# Power_supply.net
KiCad netlist of a schematic drawn in EAGLE
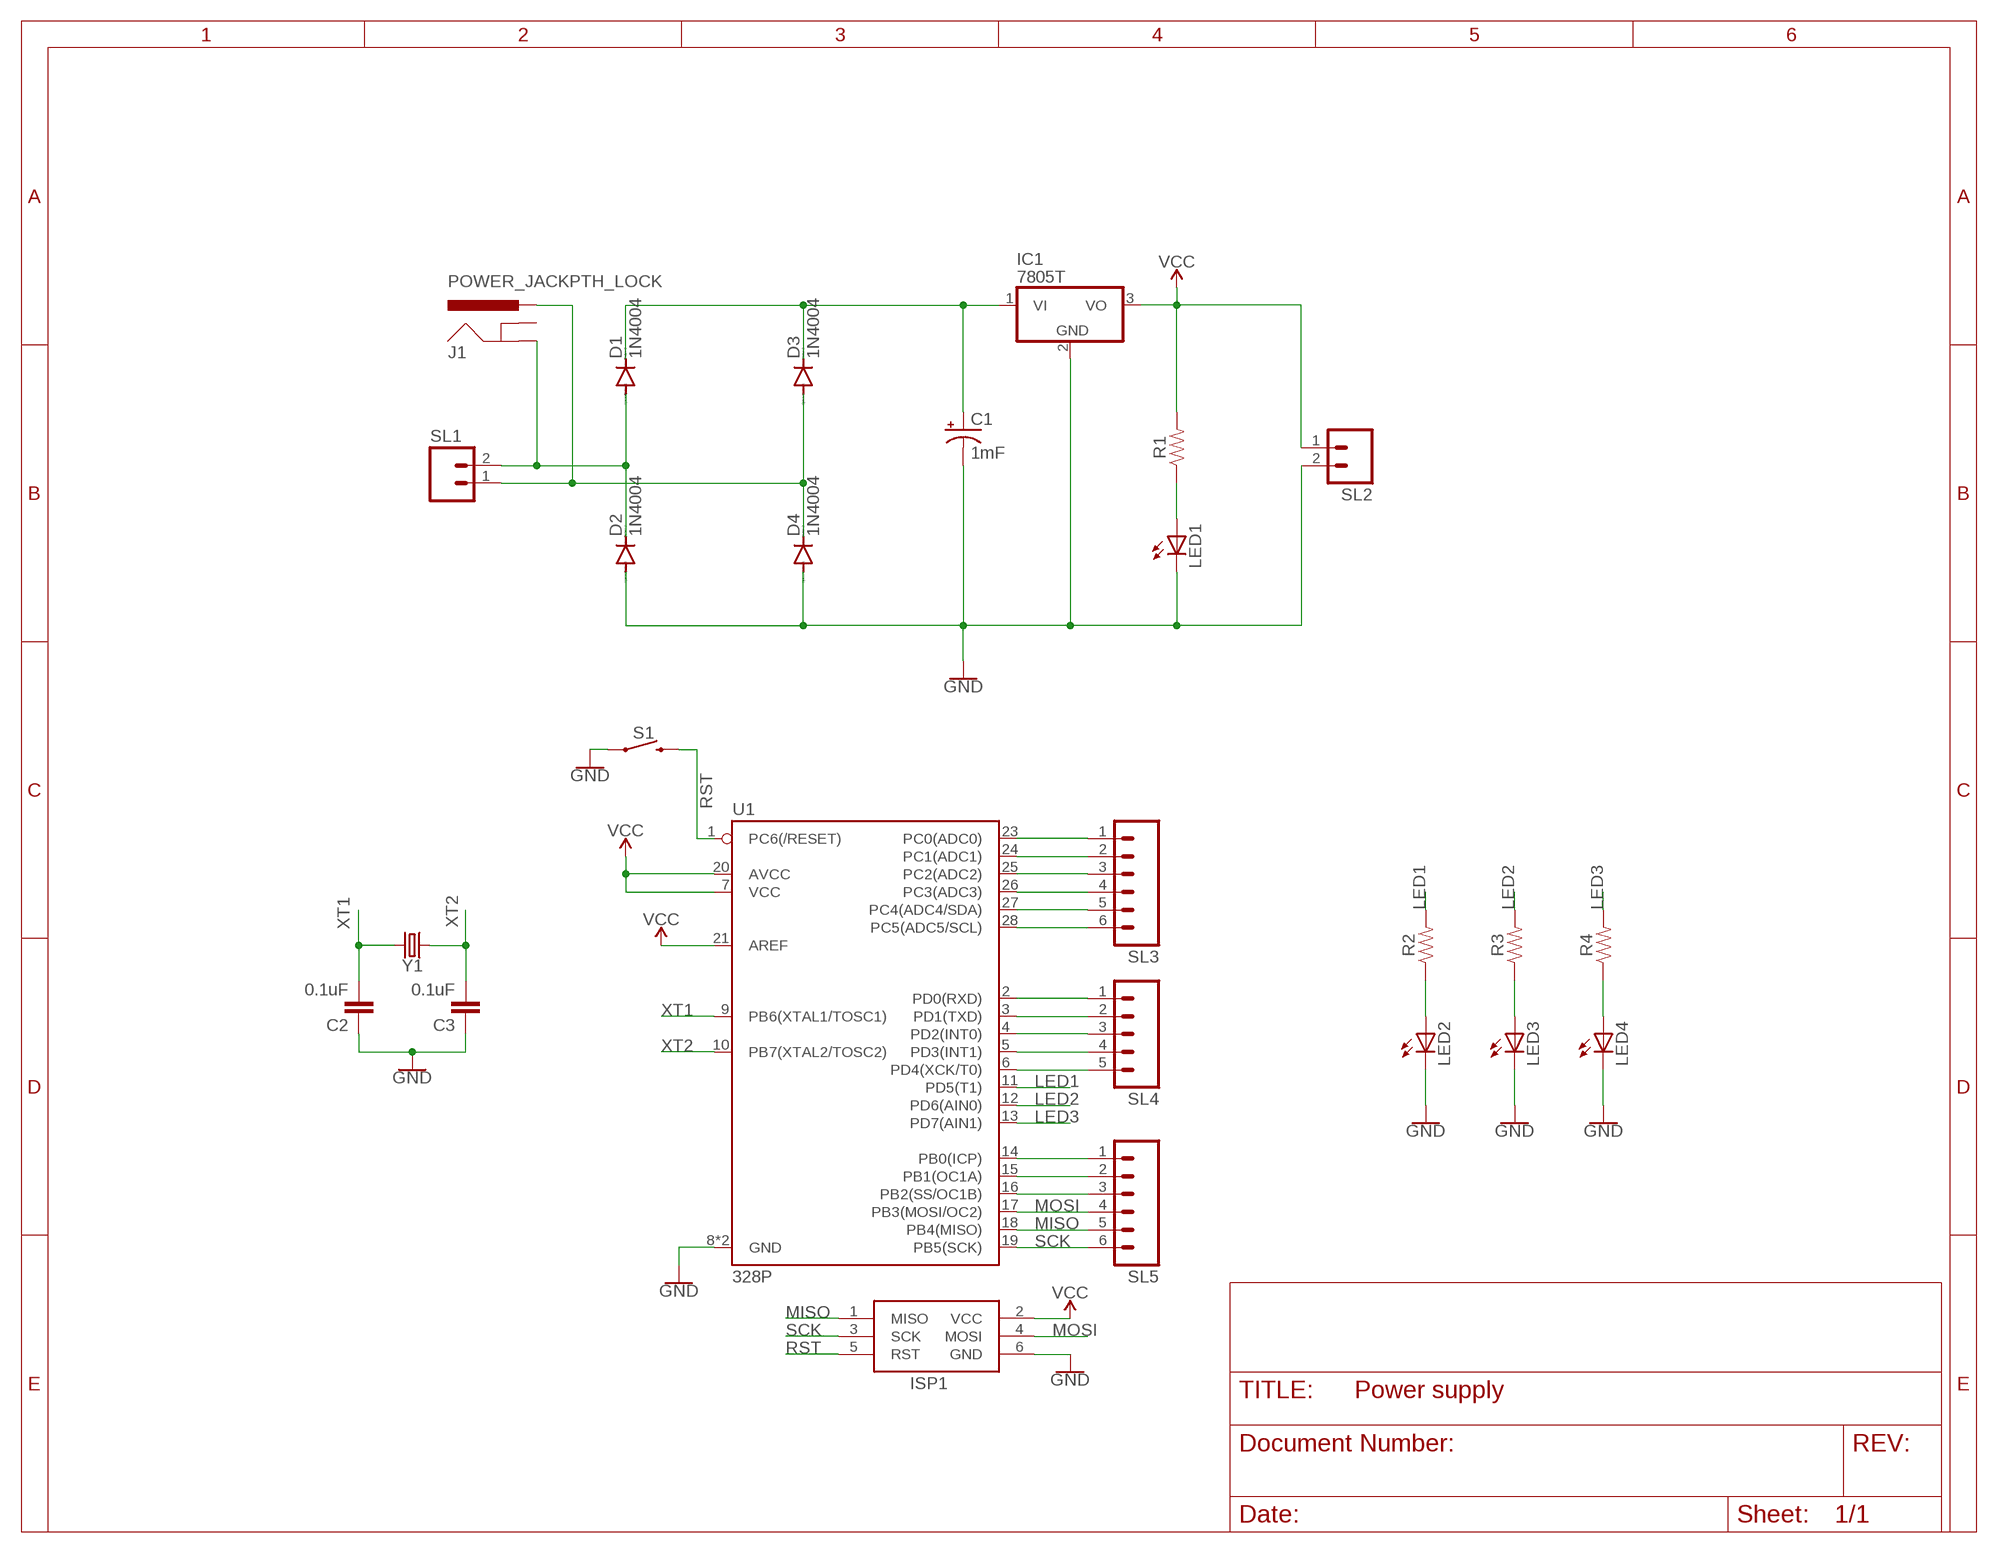
[diagram p0: schematic, sheet 1]

(export (version "E")
  (design (tool "Eeschema 10.0.6"))
  (components
    (comp (ref "C1")
      (value "1mF")
      (footprint "eagle-import:CPOL-RADIAL-5MM-10MM")
      (libsource (lib "eagle-import") (part "1000UF-RADIAL-5MM-25V-20%"))
    )
    (comp (ref "C2")
      (value "0.1uF")
      (footprint "eagle-import:CAP-PTH-SMALL-KIT")
      (libsource (lib "eagle-import") (part "0.1UF-KIT-EZ-50V-20%"))
    )
    (comp (ref "C3")
      (value "0.1uF")
      (footprint "eagle-import:CAP-PTH-SMALL-KIT")
      (libsource (lib "eagle-import") (part "0.1UF-KIT-EZ-50V-20%"))
    )
    (comp (ref "D1")
      (value "1N4004")
      (footprint "eagle-import:DO41-10")
      (libsource (lib "eagle-import") (part "1N4004"))
    )
    (comp (ref "D2")
      (value "1N4004")
      (footprint "eagle-import:DO41-10")
      (libsource (lib "eagle-import") (part "1N4004"))
    )
    (comp (ref "D3")
      (value "1N4004")
      (footprint "eagle-import:DO41-10")
      (libsource (lib "eagle-import") (part "1N4004"))
    )
    (comp (ref "D4")
      (value "1N4004")
      (footprint "eagle-import:DO41-10")
      (libsource (lib "eagle-import") (part "1N4004"))
    )
    (comp (ref "IC1")
      (value "7805T")
      (footprint "eagle-import:TO220H")
      (libsource (lib "eagle-import") (part "78T05"))
    )
    (comp (ref "ISP1")
      (value "AVRISP-6")
      (footprint "eagle-import:AVRISP")
      (libsource (lib "eagle-import") (part "AVRISP-6"))
    )
    (comp (ref "J1")
      (value "POWER_JACKPTH_LOCK")
      (footprint "eagle-import:POWER_JACK_PTH_LOCK")
      (libsource (lib "eagle-import") (part "POWER_JACKPTH_LOCK"))
    )
    (comp (ref "LED1")
      (value "LED5MM")
      (footprint "eagle-import:LED5MM")
      (libsource (lib "eagle-import") (part "LED5MM"))
    )
    (comp (ref "LED2")
      (value "LED3MM")
      (footprint "eagle-import:LED3MM")
      (libsource (lib "eagle-import") (part "LED3MM"))
    )
    (comp (ref "LED3")
      (value "LED3MM")
      (footprint "eagle-import:LED3MM")
      (libsource (lib "eagle-import") (part "LED3MM"))
    )
    (comp (ref "LED4")
      (value "LED3MM")
      (footprint "eagle-import:LED3MM")
      (libsource (lib "eagle-import") (part "LED3MM"))
    )
    (comp (ref "R1")
      (value "RESISTORAXIAL-0.3")
      (footprint "eagle-import:AXIAL-0.3")
      (libsource (lib "eagle-import") (part "RESISTORAXIAL-0.3"))
    )
    (comp (ref "R2")
      (value "RESISTORAXIAL-0.3")
      (footprint "eagle-import:AXIAL-0.3")
      (libsource (lib "eagle-import") (part "RESISTORAXIAL-0.3"))
    )
    (comp (ref "R3")
      (value "RESISTORAXIAL-0.3")
      (footprint "eagle-import:AXIAL-0.3")
      (libsource (lib "eagle-import") (part "RESISTORAXIAL-0.3"))
    )
    (comp (ref "R4")
      (value "RESISTORAXIAL-0.3")
      (footprint "eagle-import:AXIAL-0.3")
      (libsource (lib "eagle-import") (part "RESISTORAXIAL-0.3"))
    )
    (comp (ref "S1")
      (value "MOMENTARY-SWITCH-SPST-PTH-6.0MM")
      (footprint "eagle-import:TACTILE_SWITCH_PTH_6.0MM")
      (libsource (lib "eagle-import") (part "MOMENTARY-SWITCH-SPST-PTH-6.0MM"))
    )
    (comp (ref "SL1")
      (value "M02")
      (footprint "eagle-import:02P")
      (libsource (lib "eagle-import") (part "M02"))
    )
    (comp (ref "SL2")
      (value "M02")
      (footprint "eagle-import:02P")
      (libsource (lib "eagle-import") (part "M02"))
    )
    (comp (ref "SL3")
      (value "M06")
      (footprint "eagle-import:06P")
      (libsource (lib "eagle-import") (part "M06"))
    )
    (comp (ref "SL4")
      (value "M05")
      (footprint "eagle-import:05P")
      (libsource (lib "eagle-import") (part "M05"))
    )
    (comp (ref "SL5")
      (value "M06")
      (footprint "eagle-import:06P")
      (libsource (lib "eagle-import") (part "M06"))
    )
    (comp (ref "U1")
      (value "328P")
      (footprint "eagle-import:DIP28")
      (libsource (lib "eagle-import") (part "ATMEGA328P_PDIP"))
    )
    (comp (ref "Y1")
      (value "CRYSTALPTH-HC49US")
      (footprint "eagle-import:HC49US")
      (libsource (lib "eagle-import") (part "CRYSTALPTH-HC49US"))
    )
  )
  (nets
    (net (code "1") (name "/LED1") (class "Default")
      (node (ref "R2") (pin "P$2") (pinfunction "2_P$2") (pintype "passive"))
      (node (ref "U1") (pin "11") (pinfunction "PD5(T1)_11") (pintype "bidirectional"))
    )
    (net (code "2") (name "/LED2") (class "Default")
      (node (ref "R3") (pin "P$2") (pinfunction "2_P$2") (pintype "passive"))
      (node (ref "U1") (pin "12") (pinfunction "PD6(AIN0)_12") (pintype "bidirectional"))
    )
    (net (code "3") (name "/LED3") (class "Default")
      (node (ref "R4") (pin "P$2") (pinfunction "2_P$2") (pintype "passive"))
      (node (ref "U1") (pin "13") (pinfunction "PD7(AIN1)_13") (pintype "bidirectional"))
    )
    (net (code "4") (name "/MISO") (class "Default")
      (node (ref "ISP1") (pin "1") (pinfunction "MISO_1") (pintype "input"))
      (node (ref "SL5") (pin "5") (pinfunction "5_5") (pintype "passive"))
      (node (ref "U1") (pin "18") (pinfunction "PB4(MISO)_18") (pintype "bidirectional"))
    )
    (net (code "5") (name "/MOSI") (class "Default")
      (node (ref "ISP1") (pin "4") (pinfunction "MOSI_4") (pintype "output"))
      (node (ref "SL5") (pin "4") (pinfunction "4_4") (pintype "passive"))
      (node (ref "U1") (pin "17") (pinfunction "PB3(MOSI/OC2)_17") (pintype "bidirectional"))
    )
    (net (code "6") (name "/RST") (class "Default")
      (node (ref "ISP1") (pin "5") (pinfunction "RST_5") (pintype "output"))
      (node (ref "S1") (pin "3") (pinfunction "2_3") (pintype "passive"))
      (node (ref "U1") (pin "1") (pinfunction "PC6(/RESET)_1") (pintype "bidirectional"))
    )
    (net (code "7") (name "/SCK") (class "Default")
      (node (ref "ISP1") (pin "3") (pinfunction "SCK_3") (pintype "output"))
      (node (ref "SL5") (pin "6") (pinfunction "6_6") (pintype "passive"))
      (node (ref "U1") (pin "19") (pinfunction "PB5(SCK)_19") (pintype "bidirectional"))
    )
    (net (code "8") (name "/XT1") (class "Default")
      (node (ref "C2") (pin "2") (pinfunction "2_2") (pintype "passive"))
      (node (ref "U1") (pin "9") (pinfunction "PB6(XTAL1/TOSC1)_9") (pintype "bidirectional"))
      (node (ref "Y1") (pin "2") (pinfunction "2_2") (pintype "passive"))
    )
    (net (code "9") (name "/XT2") (class "Default")
      (node (ref "C3") (pin "2") (pinfunction "2_2") (pintype "passive"))
      (node (ref "U1") (pin "10") (pinfunction "PB7(XTAL2/TOSC2)_10") (pintype "bidirectional"))
      (node (ref "Y1") (pin "1") (pinfunction "1_1") (pintype "passive"))
    )
    (net (code "10") (name "GND") (class "Default")
      (node (ref "C1") (pin "-") (pinfunction "-_-") (pintype "passive"))
      (node (ref "C2") (pin "1") (pinfunction "1_1") (pintype "passive"))
      (node (ref "C3") (pin "1") (pinfunction "1_1") (pintype "passive"))
      (node (ref "D2") (pin "A") (pinfunction "A_A") (pintype "passive"))
      (node (ref "D4") (pin "A") (pinfunction "A_A") (pintype "passive"))
      (node (ref "IC1") (pin "2") (pinfunction "GND_2") (pintype "passive"))
      (node (ref "ISP1") (pin "6") (pinfunction "GND_6") (pintype "power_in"))
      (node (ref "LED1") (pin "K") (pinfunction "C_K") (pintype "passive"))
      (node (ref "LED2") (pin "K") (pinfunction "C_K") (pintype "passive"))
      (node (ref "LED3") (pin "K") (pinfunction "C_K") (pintype "passive"))
      (node (ref "LED4") (pin "K") (pinfunction "C_K") (pintype "passive"))
      (node (ref "S1") (pin "1") (pinfunction "1_1") (pintype "passive"))
      (node (ref "SL2") (pin "2") (pinfunction "2_2") (pintype "passive"))
      (node (ref "U1") (pin "22") (pinfunction "GND_22") (pintype "bidirectional"))
      (node (ref "U1") (pin "8") (pinfunction "GND_8") (pintype "bidirectional"))
    )
    (net (code "11") (name "Net-(D1-PadA)") (class "Default")
      (node (ref "D1") (pin "A") (pinfunction "A_A") (pintype "passive"))
      (node (ref "D2") (pin "C") (pinfunction "C_C") (pintype "passive"))
      (node (ref "J1") (pin "GND") (pinfunction "GND_GND") (pintype "bidirectional"))
      (node (ref "SL1") (pin "2") (pinfunction "2_2") (pintype "passive"))
    )
    (net (code "12") (name "Net-(D3-PadA)") (class "Default")
      (node (ref "D3") (pin "A") (pinfunction "A_A") (pintype "passive"))
      (node (ref "D4") (pin "C") (pinfunction "C_C") (pintype "passive"))
      (node (ref "J1") (pin "PWR") (pinfunction "PWR_PWR") (pintype "bidirectional"))
      (node (ref "SL1") (pin "1") (pinfunction "1_1") (pintype "passive"))
    )
    (net (code "13") (name "Net-(IC1-VI)") (class "Default")
      (node (ref "C1") (pin "+") (pinfunction "+_+") (pintype "passive"))
      (node (ref "D1") (pin "C") (pinfunction "C_C") (pintype "passive"))
      (node (ref "D3") (pin "C") (pinfunction "C_C") (pintype "passive"))
      (node (ref "IC1") (pin "1") (pinfunction "VI_1") (pintype "input"))
    )
    (net (code "14") (name "Net-(R1-1)") (class "Default")
      (node (ref "LED1") (pin "A") (pinfunction "A_A") (pintype "passive"))
      (node (ref "R1") (pin "P$1") (pinfunction "1_P$1") (pintype "passive"))
    )
    (net (code "15") (name "Net-(R2-1)") (class "Default")
      (node (ref "LED2") (pin "A") (pinfunction "A_A") (pintype "passive"))
      (node (ref "R2") (pin "P$1") (pinfunction "1_P$1") (pintype "passive"))
    )
    (net (code "16") (name "Net-(R3-1)") (class "Default")
      (node (ref "LED3") (pin "A") (pinfunction "A_A") (pintype "passive"))
      (node (ref "R3") (pin "P$1") (pinfunction "1_P$1") (pintype "passive"))
    )
    (net (code "17") (name "Net-(R4-1)") (class "Default")
      (node (ref "LED4") (pin "A") (pinfunction "A_A") (pintype "passive"))
      (node (ref "R4") (pin "P$1") (pinfunction "1_P$1") (pintype "passive"))
    )
    (net (code "18") (name "Net-(U1-PB0(ICP))") (class "Default")
      (node (ref "SL5") (pin "1") (pinfunction "1_1") (pintype "passive"))
      (node (ref "U1") (pin "14") (pinfunction "PB0(ICP)_14") (pintype "bidirectional"))
    )
    (net (code "19") (name "Net-(U1-PB1(OC1A))") (class "Default")
      (node (ref "SL5") (pin "2") (pinfunction "2_2") (pintype "passive"))
      (node (ref "U1") (pin "15") (pinfunction "PB1(OC1A)_15") (pintype "bidirectional"))
    )
    (net (code "20") (name "Net-(U1-PB2(SS{slash}OC1B))") (class "Default")
      (node (ref "SL5") (pin "3") (pinfunction "3_3") (pintype "passive"))
      (node (ref "U1") (pin "16") (pinfunction "PB2(SS/OC1B)_16") (pintype "bidirectional"))
    )
    (net (code "21") (name "Net-(U1-PC0(ADC0))") (class "Default")
      (node (ref "SL3") (pin "1") (pinfunction "1_1") (pintype "passive"))
      (node (ref "U1") (pin "23") (pinfunction "PC0(ADC0)_23") (pintype "bidirectional"))
    )
    (net (code "22") (name "Net-(U1-PC1(ADC1))") (class "Default")
      (node (ref "SL3") (pin "2") (pinfunction "2_2") (pintype "passive"))
      (node (ref "U1") (pin "24") (pinfunction "PC1(ADC1)_24") (pintype "bidirectional"))
    )
    (net (code "23") (name "Net-(U1-PC2(ADC2))") (class "Default")
      (node (ref "SL3") (pin "3") (pinfunction "3_3") (pintype "passive"))
      (node (ref "U1") (pin "25") (pinfunction "PC2(ADC2)_25") (pintype "bidirectional"))
    )
    (net (code "24") (name "Net-(U1-PC3(ADC3))") (class "Default")
      (node (ref "SL3") (pin "4") (pinfunction "4_4") (pintype "passive"))
      (node (ref "U1") (pin "26") (pinfunction "PC3(ADC3)_26") (pintype "bidirectional"))
    )
    (net (code "25") (name "Net-(U1-PC4(ADC4{slash}SDA))") (class "Default")
      (node (ref "SL3") (pin "5") (pinfunction "5_5") (pintype "passive"))
      (node (ref "U1") (pin "27") (pinfunction "PC4(ADC4/SDA)_27") (pintype "bidirectional"))
    )
    (net (code "26") (name "Net-(U1-PC5(ADC5{slash}SCL))") (class "Default")
      (node (ref "SL3") (pin "6") (pinfunction "6_6") (pintype "passive"))
      (node (ref "U1") (pin "28") (pinfunction "PC5(ADC5/SCL)_28") (pintype "bidirectional"))
    )
    (net (code "27") (name "Net-(U1-PD0(RXD))") (class "Default")
      (node (ref "SL4") (pin "1") (pinfunction "1_1") (pintype "passive"))
      (node (ref "U1") (pin "2") (pinfunction "PD0(RXD)_2") (pintype "bidirectional"))
    )
    (net (code "28") (name "Net-(U1-PD1(TXD))") (class "Default")
      (node (ref "SL4") (pin "2") (pinfunction "2_2") (pintype "passive"))
      (node (ref "U1") (pin "3") (pinfunction "PD1(TXD)_3") (pintype "bidirectional"))
    )
    (net (code "29") (name "Net-(U1-PD2(INT0))") (class "Default")
      (node (ref "SL4") (pin "3") (pinfunction "3_3") (pintype "passive"))
      (node (ref "U1") (pin "4") (pinfunction "PD2(INT0)_4") (pintype "bidirectional"))
    )
    (net (code "30") (name "Net-(U1-PD3(INT1))") (class "Default")
      (node (ref "SL4") (pin "4") (pinfunction "4_4") (pintype "passive"))
      (node (ref "U1") (pin "5") (pinfunction "PD3(INT1)_5") (pintype "bidirectional"))
    )
    (net (code "31") (name "Net-(U1-PD4(XCK{slash}T0))") (class "Default")
      (node (ref "SL4") (pin "5") (pinfunction "5_5") (pintype "passive"))
      (node (ref "U1") (pin "6") (pinfunction "PD4(XCK/T0)_6") (pintype "bidirectional"))
    )
    (net (code "32") (name "VCC") (class "Default")
      (node (ref "IC1") (pin "3") (pinfunction "VO_3") (pintype "passive"))
      (node (ref "ISP1") (pin "2") (pinfunction "VCC_2") (pintype "power_in"))
      (node (ref "R1") (pin "P$2") (pinfunction "2_P$2") (pintype "passive"))
      (node (ref "SL2") (pin "1") (pinfunction "1_1") (pintype "passive"))
      (node (ref "U1") (pin "20") (pinfunction "AVCC_20") (pintype "bidirectional"))
      (node (ref "U1") (pin "21") (pinfunction "AREF_21") (pintype "bidirectional"))
      (node (ref "U1") (pin "7") (pinfunction "VCC_7") (pintype "bidirectional"))
    )
    (net (code "33") (name "unconnected-(J1-PadGNDBREAK)") (class "Default")
      (node (ref "J1") (pin "GNDBREAK") (pinfunction "GNDBREAK_GNDBREAK") (pintype "bidirectional"))
    )
  )
)
